# KW-104AL.net
KiCad netlist of a schematic drawn in EAGLE
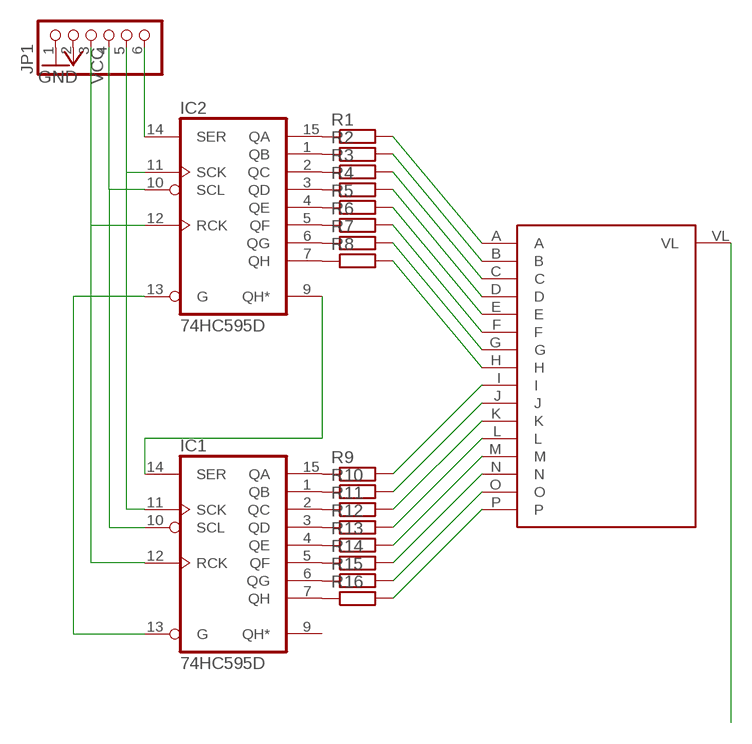
[diagram p0: schematic, sheet 1]

(export (version "E")
  (design (tool "Eeschema 10.0.6"))
  (components
    (comp (ref "IC1")
      (value "74HC595D")
      (footprint "eagle-import:SO16")
      (libsource (lib "eagle-import") (part "74595DHC"))
    )
    (comp (ref "IC2")
      (value "74HC595D")
      (footprint "eagle-import:SO16")
      (libsource (lib "eagle-import") (part "74595DHC"))
    )
    (comp (ref "JP1")
      (value "PINHD-1X6CB")
      (footprint "eagle-import:1X06-CLEANBIG")
      (libsource (lib "eagle-import") (part "PINHD-1X6CB"))
    )
    (comp (ref "R1")
      (value "R-EU_R0402")
      (footprint "eagle-import:R0402")
      (libsource (lib "eagle-import") (part "R-EU_R0402"))
    )
    (comp (ref "R2")
      (value "R-EU_R0402")
      (footprint "eagle-import:R0402")
      (libsource (lib "eagle-import") (part "R-EU_R0402"))
    )
    (comp (ref "R3")
      (value "R-EU_R0402")
      (footprint "eagle-import:R0402")
      (libsource (lib "eagle-import") (part "R-EU_R0402"))
    )
    (comp (ref "R4")
      (value "R-EU_R0402")
      (footprint "eagle-import:R0402")
      (libsource (lib "eagle-import") (part "R-EU_R0402"))
    )
    (comp (ref "R5")
      (value "R-EU_R0402")
      (footprint "eagle-import:R0402")
      (libsource (lib "eagle-import") (part "R-EU_R0402"))
    )
    (comp (ref "R6")
      (value "R-EU_R0402")
      (footprint "eagle-import:R0402")
      (libsource (lib "eagle-import") (part "R-EU_R0402"))
    )
    (comp (ref "R7")
      (value "R-EU_R0402")
      (footprint "eagle-import:R0402")
      (libsource (lib "eagle-import") (part "R-EU_R0402"))
    )
    (comp (ref "R8")
      (value "R-EU_R0402")
      (footprint "eagle-import:R0402")
      (libsource (lib "eagle-import") (part "R-EU_R0402"))
    )
    (comp (ref "R9")
      (value "R-EU_R0402")
      (footprint "eagle-import:R0402")
      (libsource (lib "eagle-import") (part "R-EU_R0402"))
    )
    (comp (ref "R10")
      (value "R-EU_R0402")
      (footprint "eagle-import:R0402")
      (libsource (lib "eagle-import") (part "R-EU_R0402"))
    )
    (comp (ref "R11")
      (value "R-EU_R0402")
      (footprint "eagle-import:R0402")
      (libsource (lib "eagle-import") (part "R-EU_R0402"))
    )
    (comp (ref "R12")
      (value "R-EU_R0402")
      (footprint "eagle-import:R0402")
      (libsource (lib "eagle-import") (part "R-EU_R0402"))
    )
    (comp (ref "R13")
      (value "R-EU_R0402")
      (footprint "eagle-import:R0402")
      (libsource (lib "eagle-import") (part "R-EU_R0402"))
    )
    (comp (ref "R14")
      (value "R-EU_R0402")
      (footprint "eagle-import:R0402")
      (libsource (lib "eagle-import") (part "R-EU_R0402"))
    )
    (comp (ref "R15")
      (value "R-EU_R0402")
      (footprint "eagle-import:R0402")
      (libsource (lib "eagle-import") (part "R-EU_R0402"))
    )
    (comp (ref "R16")
      (value "R-EU_R0402")
      (footprint "eagle-import:R0402")
      (libsource (lib "eagle-import") (part "R-EU_R0402"))
    )
    (comp (ref "U$1")
      (value "1.27KW-104AL")
      (footprint "eagle-import:127")
      (libsource (lib "eagle-import") (part "1.27KW-104AL"))
    )
  )
  (nets
    (net (code "1") (name "GND") (class "Default")
      (node (ref "JP1") (pin "1") (pinfunction "1_1") (pintype "passive"))
    )
    (net (code "2") (name "Net-(IC1A-G)") (class "Default")
      (node (ref "IC1") (pin "13") (pinfunction "G_13") (pintype "input"))
      (node (ref "IC2") (pin "13") (pinfunction "G_13") (pintype "input"))
    )
    (net (code "3") (name "Net-(IC1A-QA)") (class "Default")
      (node (ref "IC1") (pin "15") (pinfunction "QA_15") (pintype "tri_state"))
      (node (ref "R9") (pin "1") (pinfunction "1_1") (pintype "passive"))
    )
    (net (code "4") (name "Net-(IC1A-QB)") (class "Default")
      (node (ref "IC1") (pin "1") (pinfunction "QB_1") (pintype "tri_state"))
      (node (ref "R10") (pin "1") (pinfunction "1_1") (pintype "passive"))
    )
    (net (code "5") (name "Net-(IC1A-QC)") (class "Default")
      (node (ref "IC1") (pin "2") (pinfunction "QC_2") (pintype "tri_state"))
      (node (ref "R11") (pin "1") (pinfunction "1_1") (pintype "passive"))
    )
    (net (code "6") (name "Net-(IC1A-QD)") (class "Default")
      (node (ref "IC1") (pin "3") (pinfunction "QD_3") (pintype "tri_state"))
      (node (ref "R12") (pin "1") (pinfunction "1_1") (pintype "passive"))
    )
    (net (code "7") (name "Net-(IC1A-QE)") (class "Default")
      (node (ref "IC1") (pin "4") (pinfunction "QE_4") (pintype "tri_state"))
      (node (ref "R13") (pin "1") (pinfunction "1_1") (pintype "passive"))
    )
    (net (code "8") (name "Net-(IC1A-QF)") (class "Default")
      (node (ref "IC1") (pin "5") (pinfunction "QF_5") (pintype "tri_state"))
      (node (ref "R14") (pin "1") (pinfunction "1_1") (pintype "passive"))
    )
    (net (code "9") (name "Net-(IC1A-QG)") (class "Default")
      (node (ref "IC1") (pin "6") (pinfunction "QG_6") (pintype "tri_state"))
      (node (ref "R15") (pin "1") (pinfunction "1_1") (pintype "passive"))
    )
    (net (code "10") (name "Net-(IC1A-QH)") (class "Default")
      (node (ref "IC1") (pin "7") (pinfunction "QH_7") (pintype "tri_state"))
      (node (ref "R16") (pin "1") (pinfunction "1_1") (pintype "passive"))
    )
    (net (code "11") (name "Net-(IC1A-RCK)") (class "Default")
      (node (ref "IC1") (pin "12") (pinfunction "RCK_12") (pintype "input"))
      (node (ref "IC2") (pin "12") (pinfunction "RCK_12") (pintype "input"))
      (node (ref "JP1") (pin "3") (pinfunction "3_3") (pintype "passive"))
    )
    (net (code "12") (name "Net-(IC1A-SCK)") (class "Default")
      (node (ref "IC1") (pin "11") (pinfunction "SCK_11") (pintype "input"))
      (node (ref "IC2") (pin "11") (pinfunction "SCK_11") (pintype "input"))
      (node (ref "JP1") (pin "5") (pinfunction "5_5") (pintype "passive"))
    )
    (net (code "13") (name "Net-(IC1A-SCL)") (class "Default")
      (node (ref "IC1") (pin "10") (pinfunction "SCL_10") (pintype "input"))
      (node (ref "IC2") (pin "10") (pinfunction "SCL_10") (pintype "input"))
      (node (ref "JP1") (pin "4") (pinfunction "4_4") (pintype "passive"))
    )
    (net (code "14") (name "Net-(IC1A-SER)") (class "Default")
      (node (ref "IC1") (pin "14") (pinfunction "SER_14") (pintype "input"))
      (node (ref "IC2") (pin "9") (pinfunction "QH*_9") (pintype "tri_state"))
    )
    (net (code "15") (name "Net-(IC2A-QA)") (class "Default")
      (node (ref "IC2") (pin "15") (pinfunction "QA_15") (pintype "tri_state"))
      (node (ref "R1") (pin "1") (pinfunction "1_1") (pintype "passive"))
    )
    (net (code "16") (name "Net-(IC2A-QB)") (class "Default")
      (node (ref "IC2") (pin "1") (pinfunction "QB_1") (pintype "tri_state"))
      (node (ref "R2") (pin "1") (pinfunction "1_1") (pintype "passive"))
    )
    (net (code "17") (name "Net-(IC2A-QC)") (class "Default")
      (node (ref "IC2") (pin "2") (pinfunction "QC_2") (pintype "tri_state"))
      (node (ref "R3") (pin "1") (pinfunction "1_1") (pintype "passive"))
    )
    (net (code "18") (name "Net-(IC2A-QD)") (class "Default")
      (node (ref "IC2") (pin "3") (pinfunction "QD_3") (pintype "tri_state"))
      (node (ref "R4") (pin "1") (pinfunction "1_1") (pintype "passive"))
    )
    (net (code "19") (name "Net-(IC2A-QE)") (class "Default")
      (node (ref "IC2") (pin "4") (pinfunction "QE_4") (pintype "tri_state"))
      (node (ref "R5") (pin "1") (pinfunction "1_1") (pintype "passive"))
    )
    (net (code "20") (name "Net-(IC2A-QF)") (class "Default")
      (node (ref "IC2") (pin "5") (pinfunction "QF_5") (pintype "tri_state"))
      (node (ref "R6") (pin "1") (pinfunction "1_1") (pintype "passive"))
    )
    (net (code "21") (name "Net-(IC2A-QG)") (class "Default")
      (node (ref "IC2") (pin "6") (pinfunction "QG_6") (pintype "tri_state"))
      (node (ref "R7") (pin "1") (pinfunction "1_1") (pintype "passive"))
    )
    (net (code "22") (name "Net-(IC2A-QH)") (class "Default")
      (node (ref "IC2") (pin "7") (pinfunction "QH_7") (pintype "tri_state"))
      (node (ref "R8") (pin "1") (pinfunction "1_1") (pintype "passive"))
    )
    (net (code "23") (name "Net-(IC2A-SER)") (class "Default")
      (node (ref "IC2") (pin "14") (pinfunction "SER_14") (pintype "input"))
      (node (ref "JP1") (pin "6") (pinfunction "6_6") (pintype "passive"))
    )
    (net (code "24") (name "Net-(R1-Pad2)") (class "Default")
      (node (ref "R1") (pin "2") (pinfunction "2_2") (pintype "passive"))
      (node (ref "U$1") (pin "A") (pinfunction "A_A") (pintype "bidirectional"))
    )
    (net (code "25") (name "Net-(R2-Pad2)") (class "Default")
      (node (ref "R2") (pin "2") (pinfunction "2_2") (pintype "passive"))
      (node (ref "U$1") (pin "B") (pinfunction "B_B") (pintype "bidirectional"))
    )
    (net (code "26") (name "Net-(R3-Pad2)") (class "Default")
      (node (ref "R3") (pin "2") (pinfunction "2_2") (pintype "passive"))
      (node (ref "U$1") (pin "C") (pinfunction "C_C") (pintype "bidirectional"))
    )
    (net (code "27") (name "Net-(R4-Pad2)") (class "Default")
      (node (ref "R4") (pin "2") (pinfunction "2_2") (pintype "passive"))
      (node (ref "U$1") (pin "D") (pinfunction "D_D") (pintype "bidirectional"))
    )
    (net (code "28") (name "Net-(R5-Pad2)") (class "Default")
      (node (ref "R5") (pin "2") (pinfunction "2_2") (pintype "passive"))
      (node (ref "U$1") (pin "E") (pinfunction "E_E") (pintype "bidirectional"))
    )
    (net (code "29") (name "Net-(R6-Pad2)") (class "Default")
      (node (ref "R6") (pin "2") (pinfunction "2_2") (pintype "passive"))
      (node (ref "U$1") (pin "F") (pinfunction "F_F") (pintype "bidirectional"))
    )
    (net (code "30") (name "Net-(R7-Pad2)") (class "Default")
      (node (ref "R7") (pin "2") (pinfunction "2_2") (pintype "passive"))
      (node (ref "U$1") (pin "G") (pinfunction "G_G") (pintype "bidirectional"))
    )
    (net (code "31") (name "Net-(R8-Pad2)") (class "Default")
      (node (ref "R8") (pin "2") (pinfunction "2_2") (pintype "passive"))
      (node (ref "U$1") (pin "H") (pinfunction "H_H") (pintype "bidirectional"))
    )
    (net (code "32") (name "Net-(R9-Pad2)") (class "Default")
      (node (ref "R9") (pin "2") (pinfunction "2_2") (pintype "passive"))
      (node (ref "U$1") (pin "I") (pinfunction "I_I") (pintype "bidirectional"))
    )
    (net (code "33") (name "Net-(R10-Pad2)") (class "Default")
      (node (ref "R10") (pin "2") (pinfunction "2_2") (pintype "passive"))
      (node (ref "U$1") (pin "J") (pinfunction "J_J") (pintype "bidirectional"))
    )
    (net (code "34") (name "Net-(R11-Pad2)") (class "Default")
      (node (ref "R11") (pin "2") (pinfunction "2_2") (pintype "passive"))
      (node (ref "U$1") (pin "K") (pinfunction "K_K") (pintype "bidirectional"))
    )
    (net (code "35") (name "Net-(R12-Pad2)") (class "Default")
      (node (ref "R12") (pin "2") (pinfunction "2_2") (pintype "passive"))
      (node (ref "U$1") (pin "L") (pinfunction "L_L") (pintype "bidirectional"))
    )
    (net (code "36") (name "Net-(R13-Pad2)") (class "Default")
      (node (ref "R13") (pin "2") (pinfunction "2_2") (pintype "passive"))
      (node (ref "U$1") (pin "M") (pinfunction "M_M") (pintype "bidirectional"))
    )
    (net (code "37") (name "Net-(R14-Pad2)") (class "Default")
      (node (ref "R14") (pin "2") (pinfunction "2_2") (pintype "passive"))
      (node (ref "U$1") (pin "N") (pinfunction "N_N") (pintype "bidirectional"))
    )
    (net (code "38") (name "Net-(R15-Pad2)") (class "Default")
      (node (ref "R15") (pin "2") (pinfunction "2_2") (pintype "passive"))
      (node (ref "U$1") (pin "O") (pinfunction "O_O") (pintype "bidirectional"))
    )
    (net (code "39") (name "Net-(R16-Pad2)") (class "Default")
      (node (ref "R16") (pin "2") (pinfunction "2_2") (pintype "passive"))
      (node (ref "U$1") (pin "P") (pinfunction "P_P") (pintype "bidirectional"))
    )
    (net (code "40") (name "VCC") (class "Default")
      (node (ref "JP1") (pin "2") (pinfunction "2_2") (pintype "passive"))
    )
    (net (code "41") (name "unconnected-(IC1A-QH*-Pad9)") (class "Default")
      (node (ref "IC1") (pin "9") (pinfunction "QH*_9") (pintype "tri_state"))
    )
    (net (code "42") (name "unconnected-(U$1-PadVL)") (class "Default")
      (node (ref "U$1") (pin "VL") (pinfunction "VL_VL") (pintype "bidirectional"))
    )
  )
)
